# UART.net
KiCad netlist of a schematic drawn in Altium Designer
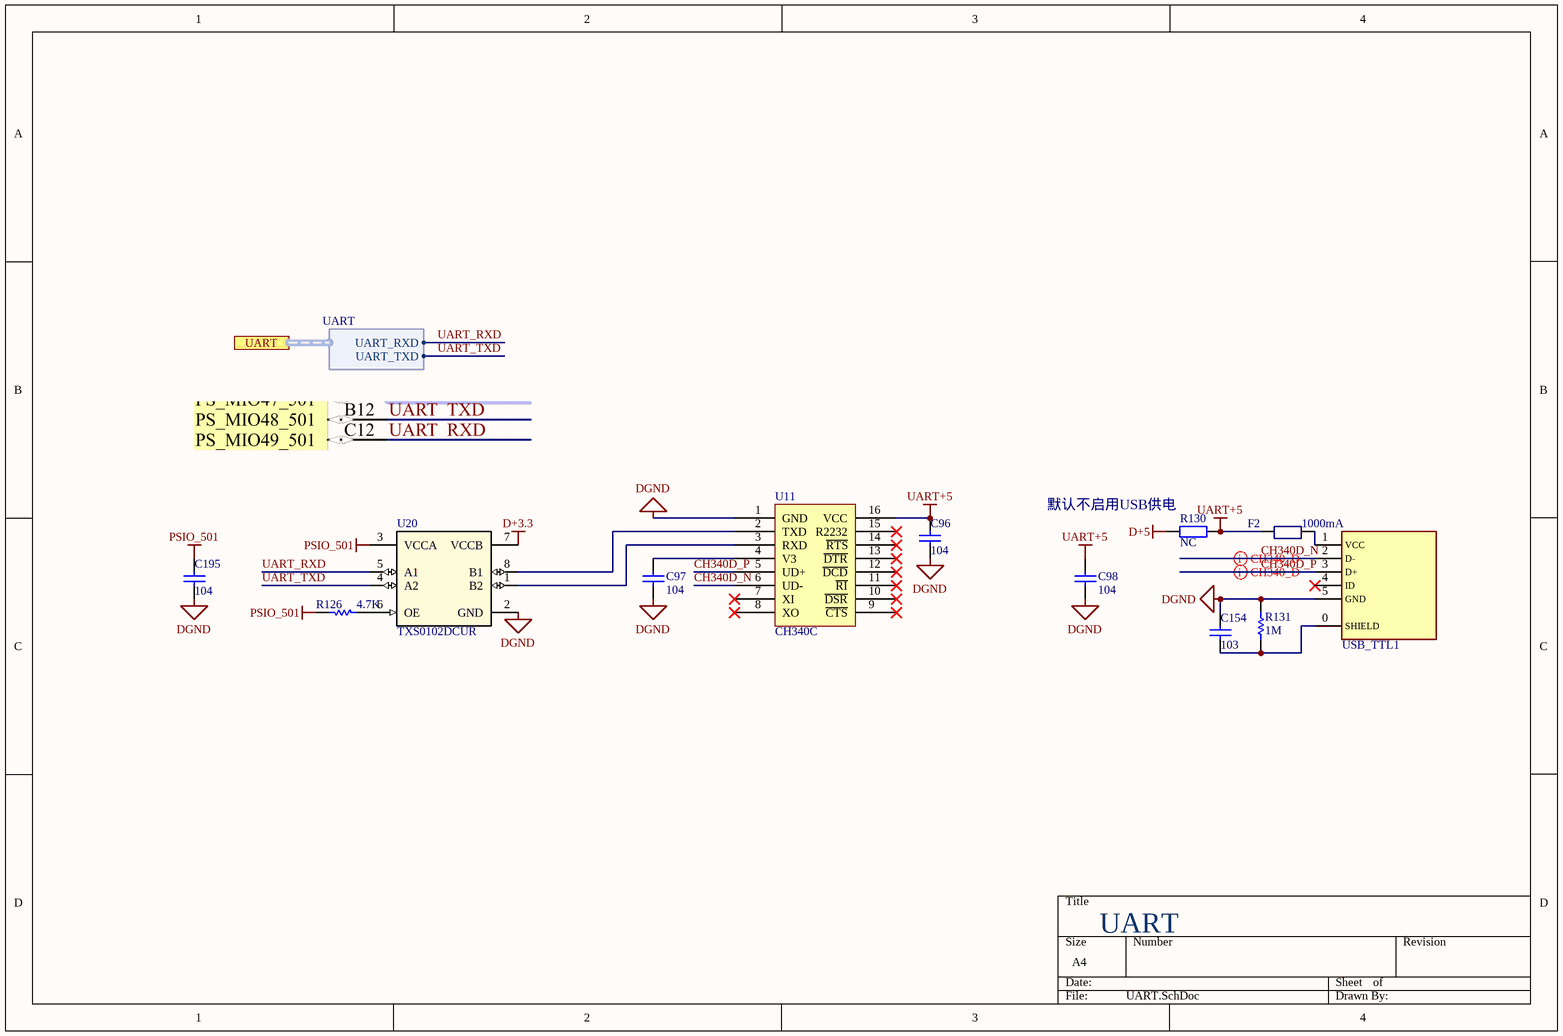
[diagram p0: UART.SchDoc]

(export (version "E")
  (design (tool "Eeschema 10.0.6"))
  (components
    (comp (ref "C96")
      (value "104")
      (footprint "C 0402_LL")
      (description "Capacitor")
      (fields (field (name "PUBLISHER") "Altium Limited"))
      (libsource (lib "Miscellaneous Devices") (part "Cap"))
    )
    (comp (ref "C97")
      (value "104")
      (footprint "C 0402_LL")
      (description "Capacitor")
      (fields (field (name "PUBLISHER") "Altium Limited"))
      (libsource (lib "Miscellaneous Devices") (part "Cap"))
    )
    (comp (ref "C98")
      (value "104")
      (footprint "C 0402_LL")
      (description "Capacitor")
      (fields (field (name "PUBLISHER") "Altium Limited"))
      (libsource (lib "Miscellaneous Devices") (part "Cap"))
    )
    (comp (ref "C154")
      (value "103")
      (footprint "C 0603_L")
      (description "Capacitor")
      (fields (field (name "PUBLISHER") "Altium Limited"))
      (libsource (lib "Miscellaneous Devices") (part "Cap"))
    )
    (comp (ref "C195")
      (value "104")
      (footprint "C 0402_LL")
      (description "Capacitor")
      (fields (field (name "PUBLISHER") "Altium Limited"))
      (libsource (lib "Miscellaneous Devices") (part "Cap"))
    )
    (comp (ref "F2") (value "1000mA") (footprint "FU 0805") (libsource (lib "Sean") (part "PTC")))
    (comp (ref "R126")
      (value "4.7K")
      (footprint "R 0603_L")
      (description "Resistor")
      (fields (field (name "PUBLISHER") "Altium Limited"))
      (libsource (lib "Miscellaneous Devices") (part "Res1"))
    )
    (comp (ref "R130")
      (value "NC")
      (footprint "R 1206_L")
      (description "Resistor")
      (fields (field (name "PUBLISHER") "Altium Limited"))
      (libsource (lib "Miscellaneous Devices") (part "Res2"))
    )
    (comp (ref "R131")
      (value "1M")
      (footprint "R 0603_L")
      (description "Resistor")
      (fields (field (name "PUBLISHER") "Altium Limited"))
      (libsource (lib "Miscellaneous Devices") (part "Res1"))
    )
    (comp (ref "U11")
      (value "CH340C")
      (footprint "SOP16_L")
      (description "CH340G")
      (libsource (lib "Sean") (part "CH340G"))
    )
    (comp (ref "U20")
      (value "TXS0102DCUR")
      (footprint "DCU0008A_N")
      (description "No Description Available")
      (fields (field (name "COPYRIGHT") "Copyright (C) 2022 Ultra Librarian. All rights reserved."))
      (libsource (lib "ZYNQ7010_add") (part "TXS0102DCUR"))
    )
    (comp (ref "USB_TTL1")
      (value "USB_miniB,microB")
      (footprint "USB-MINI-A")
      (libsource (lib "Schlib1") (part "USB_miniB,microB"))
    )
  )
  (nets
    (net (code "2") (name "/CH340D_N") (class "Default")
      (node (ref "U11") (pin "6") (pinfunction "UD-_6") (pintype "passive"))
      (node (ref "USB_TTL1") (pin "2") (pinfunction "D-_2") (pintype "passive"))
    )
    (net (code "3") (name "/CH340D_P") (class "Default")
      (node (ref "U11") (pin "5") (pinfunction "UD+_5") (pintype "passive"))
      (node (ref "USB_TTL1") (pin "3") (pinfunction "D+_3") (pintype "passive"))
    )
    (net (code "4") (name "/UART_RXD") (class "Default")
      (node (ref "U20") (pin "5") (pinfunction "A1_5") (pintype "bidirectional"))
    )
    (net (code "5") (name "/UART_TXD") (class "Default")
      (node (ref "U20") (pin "4") (pinfunction "A2_4") (pintype "bidirectional"))
    )
    (net (code "7") (name "D+3.3") (class "Default")
      (node (ref "U20") (pin "7") (pinfunction "VCCB_7") (pintype "power_in"))
    )
    (net (code "8") (name "D+5") (class "Default")
      (node (ref "R130") (pin "2") (pinfunction "2_2") (pintype "passive"))
    )
    (net (code "9") (name "DGND") (class "Default")
      (node (ref "C154") (pin "1") (pinfunction "1_1") (pintype "passive"))
      (node (ref "C195") (pin "1") (pinfunction "1_1") (pintype "passive"))
      (node (ref "C96") (pin "1") (pinfunction "1_1") (pintype "passive"))
      (node (ref "C97") (pin "2") (pinfunction "2_2") (pintype "passive"))
      (node (ref "C98") (pin "1") (pinfunction "1_1") (pintype "passive"))
      (node (ref "R131") (pin "2") (pinfunction "2_2") (pintype "passive"))
      (node (ref "U11") (pin "1") (pinfunction "GND_1") (pintype "passive"))
      (node (ref "U20") (pin "2") (pinfunction "GND_2") (pintype "power_in"))
      (node (ref "USB_TTL1") (pin "5") (pinfunction "GND_5") (pintype "passive"))
    )
    (net (code "10") (name "Net-(U11-RXD)") (class "Default")
      (node (ref "U11") (pin "3") (pinfunction "RXD_3") (pintype "passive"))
      (node (ref "U20") (pin "1") (pinfunction "B2_1") (pintype "bidirectional"))
    )
    (net (code "11") (name "Net-(U11-TXD)") (class "Default")
      (node (ref "U11") (pin "2") (pinfunction "TXD_2") (pintype "passive"))
      (node (ref "U20") (pin "8") (pinfunction "B1_8") (pintype "bidirectional"))
    )
    (net (code "12") (name "Net-(U11-V3)") (class "Default")
      (node (ref "C97") (pin "1") (pinfunction "1_1") (pintype "passive"))
      (node (ref "U11") (pin "4") (pinfunction "V3_4") (pintype "passive"))
    )
    (net (code "13") (name "Net-(U20-OE)") (class "Default")
      (node (ref "R126") (pin "1") (pinfunction "1_1") (pintype "passive"))
      (node (ref "U20") (pin "6") (pinfunction "OE_6") (pintype "input"))
    )
    (net (code "14") (name "Net-(USB_TTL1-SHIELD)") (class "Default")
      (node (ref "C154") (pin "2") (pinfunction "2_2") (pintype "passive"))
      (node (ref "R131") (pin "1") (pinfunction "1_1") (pintype "passive"))
      (node (ref "USB_TTL1") (pin "0") (pinfunction "SHIELD_0") (pintype "passive"))
    )
    (net (code "15") (name "Net-(USB_TTL1-VCC)") (class "Default")
      (node (ref "F2") (pin "2") (pinfunction "2_2") (pintype "passive"))
      (node (ref "USB_TTL1") (pin "1") (pinfunction "VCC_1") (pintype "passive"))
    )
    (net (code "16") (name "PSIO_501") (class "Default")
      (node (ref "C195") (pin "2") (pinfunction "2_2") (pintype "passive"))
      (node (ref "R126") (pin "2") (pinfunction "2_2") (pintype "passive"))
      (node (ref "U20") (pin "3") (pinfunction "VCCA_3") (pintype "power_in"))
    )
    (net (code "17") (name "UART+5") (class "Default")
      (node (ref "C96") (pin "2") (pinfunction "2_2") (pintype "passive"))
      (node (ref "C98") (pin "2") (pinfunction "2_2") (pintype "passive"))
      (node (ref "F2") (pin "1") (pinfunction "1_1") (pintype "passive"))
      (node (ref "R130") (pin "1") (pinfunction "1_1") (pintype "passive"))
      (node (ref "U11") (pin "16") (pinfunction "VCC_16") (pintype "passive"))
    )
    (net (code "18") (name "unconnected-(U11-R2232-Pad15)") (class "Default")
      (node (ref "U11") (pin "15") (pinfunction "R2232_15") (pintype "passive+no_connect"))
    )
    (net (code "19") (name "unconnected-(U11-XI-Pad7)") (class "Default")
      (node (ref "U11") (pin "7") (pinfunction "XI_7") (pintype "passive+no_connect"))
    )
    (net (code "20") (name "unconnected-(U11-XO-Pad8)") (class "Default")
      (node (ref "U11") (pin "8") (pinfunction "XO_8") (pintype "passive+no_connect"))
    )
    (net (code "21") (name "unconnected-(U11-~{CTS}-Pad9)") (class "Default")
      (node (ref "U11") (pin "9") (pinfunction "~{CTS}_9") (pintype "passive+no_connect"))
    )
    (net (code "22") (name "unconnected-(U11-~{DCD}-Pad12)") (class "Default")
      (node (ref "U11") (pin "12") (pinfunction "~{DCD}_12") (pintype "passive+no_connect"))
    )
    (net (code "23") (name "unconnected-(U11-~{DSR}-Pad10)") (class "Default")
      (node (ref "U11") (pin "10") (pinfunction "~{DSR}_10") (pintype "passive+no_connect"))
    )
    (net (code "24") (name "unconnected-(U11-~{DTR}-Pad13)") (class "Default")
      (node (ref "U11") (pin "13") (pinfunction "~{DTR}_13") (pintype "passive+no_connect"))
    )
    (net (code "25") (name "unconnected-(U11-~{RI}-Pad11)") (class "Default")
      (node (ref "U11") (pin "11") (pinfunction "~{RI}_11") (pintype "passive+no_connect"))
    )
    (net (code "26") (name "unconnected-(U11-~{RTS}-Pad14)") (class "Default")
      (node (ref "U11") (pin "14") (pinfunction "~{RTS}_14") (pintype "passive+no_connect"))
    )
    (net (code "27") (name "unconnected-(USB_TTL1-ID-Pad4)") (class "Default")
      (node (ref "USB_TTL1") (pin "4") (pinfunction "ID_4") (pintype "passive+no_connect"))
    )
  )
)
